# bpod_stepper_1_4_4.net
KiCad netlist of a schematic drawn in EAGLE
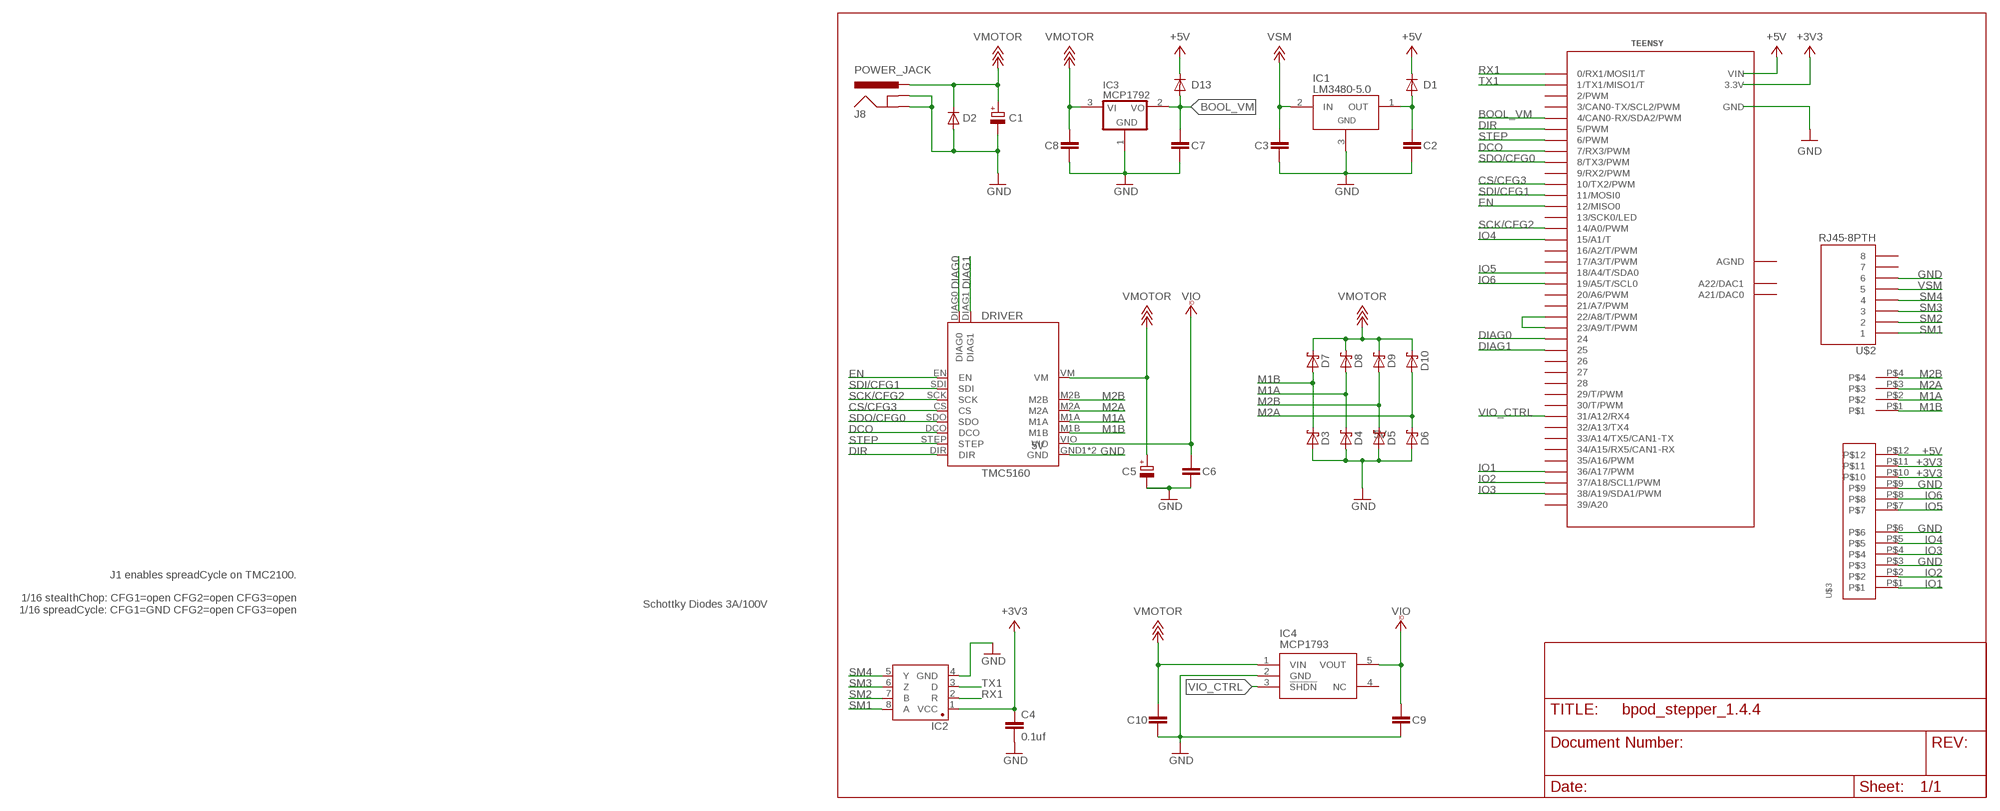
[diagram p0: schematic, sheet 1]

(export (version "E")
  (design (tool "Eeschema 10.0.6"))
  (components
    (comp (ref "C1")
      (value "CPOL-EUG")
      (footprint "eagle-import:PANASONIC_G")
      (libsource (lib "eagle-import") (part "CPOL-EUG"))
    )
    (comp (ref "C2")
      (value "0.1uf")
      (footprint "eagle-import:1206@1")
      (libsource (lib "eagle-import") (part "CAP1206"))
    )
    (comp (ref "C3")
      (value "0.1uf")
      (footprint "eagle-import:1206@1")
      (libsource (lib "eagle-import") (part "CAP1206"))
    )
    (comp (ref "C4")
      (value "0.1uf")
      (footprint "eagle-import:1206@1")
      (libsource (lib "eagle-import") (part "CAP1206"))
    )
    (comp (ref "C5")
      (value "CPOL-EUG")
      (footprint "eagle-import:PANASONIC_G")
      (libsource (lib "eagle-import") (part "CPOL-EUG"))
    )
    (comp (ref "C6")
      (value "0.1nf")
      (footprint "eagle-import:1206@1")
      (libsource (lib "eagle-import") (part "CAP1206"))
    )
    (comp (ref "C7")
      (value "2.2uf")
      (footprint "eagle-import:1206@1")
      (libsource (lib "eagle-import") (part "CAP1206"))
    )
    (comp (ref "C8")
      (value "2.2uf")
      (footprint "eagle-import:1206@1")
      (libsource (lib "eagle-import") (part "CAP1206"))
    )
    (comp (ref "C9")
      (value "2.2uf")
      (footprint "eagle-import:1206@1")
      (libsource (lib "eagle-import") (part "CAP1206"))
    )
    (comp (ref "C10")
      (value "2.2uf")
      (footprint "eagle-import:1206@1")
      (libsource (lib "eagle-import") (part "CAP1206"))
    )
    (comp (ref "D1")
      (value "MBR0520LT")
      (footprint "eagle-import:SOD123")
      (libsource (lib "eagle-import") (part "MBR0520LT"))
    )
    (comp (ref "D2")
      (value "DIODE-DO214AA")
      (footprint "eagle-import:DO214AA")
      (libsource (lib "eagle-import") (part "DIODE-DO214AA"))
    )
    (comp (ref "D3")
      (value "S310FA")
      (footprint "eagle-import:SOD123")
      (libsource (lib "eagle-import") (part "D_SCHOTTKY-SOD123"))
    )
    (comp (ref "D4")
      (value "S310FA")
      (footprint "eagle-import:SOD123")
      (libsource (lib "eagle-import") (part "D_SCHOTTKY-SOD123"))
    )
    (comp (ref "D5")
      (value "S310FA")
      (footprint "eagle-import:SOD123")
      (libsource (lib "eagle-import") (part "D_SCHOTTKY-SOD123"))
    )
    (comp (ref "D6")
      (value "S310FA")
      (footprint "eagle-import:SOD123")
      (libsource (lib "eagle-import") (part "D_SCHOTTKY-SOD123"))
    )
    (comp (ref "D7")
      (value "S310FA")
      (footprint "eagle-import:SOD123")
      (libsource (lib "eagle-import") (part "D_SCHOTTKY-SOD123"))
    )
    (comp (ref "D8")
      (value "S310FA")
      (footprint "eagle-import:SOD123")
      (libsource (lib "eagle-import") (part "D_SCHOTTKY-SOD123"))
    )
    (comp (ref "D9")
      (value "S310FA")
      (footprint "eagle-import:SOD123")
      (libsource (lib "eagle-import") (part "D_SCHOTTKY-SOD123"))
    )
    (comp (ref "D10")
      (value "S310FA")
      (footprint "eagle-import:SOD123")
      (libsource (lib "eagle-import") (part "D_SCHOTTKY-SOD123"))
    )
    (comp (ref "D13")
      (value "MBR0520LT")
      (footprint "eagle-import:SOD123")
      (libsource (lib "eagle-import") (part "MBR0520LT"))
    )
    (comp (ref "DRIVER")
      (value "TMC5160")
      (footprint "eagle-import:TMC5160")
      (libsource (lib "eagle-import") (part "TMC5160"))
    )
    (comp (ref "IC1")
      (value "LM3480-5.0")
      (footprint "eagle-import:SOT-23-3")
      (libsource (lib "eagle-import") (part "LM3480-5.0"))
    )
    (comp (ref "IC2")
      (value "SN65HVD31DR")
      (footprint "eagle-import:SO08")
      (libsource (lib "eagle-import") (part "SN65HVD31DR"))
    )
    (comp (ref "IC3")
      (value "MCP1792")
      (footprint "eagle-import:SOT23A_MICROCHIP_CB")
      (libsource (lib "eagle-import") (part "MCP170302E/CB-12"))
    )
    (comp (ref "IC4")
      (value "MCP1793")
      (footprint "eagle-import:SOT23-5")
      (libsource (lib "eagle-import") (part "MCP1793"))
    )
    (comp (ref "J8")
      (value "POWER_JACK")
      (footprint "eagle-import:POWER_JACK_PTH")
      (libsource (lib "eagle-import") (part "POWER_JACK"))
    )
    (comp (ref "TEENSY")
      (value "TEENSY_3.6_DIL")
      (footprint "eagle-import:TEENSY_3.6_DIL")
      (libsource (lib "eagle-import") (part "TEENSY_3.6_DIL"))
    )
    (comp (ref "U$2")
      (value "RJ45-8PTH")
      (footprint "eagle-import:RJ45-8")
      (libsource (lib "eagle-import") (part "RJ45-8PTH"))
    )
    (comp (ref "U$3")
      (value "12POS_MOLEX_SOCKET")
      (footprint "eagle-import:12POS_MOLEX_SOCKET")
      (libsource (lib "eagle-import") (part "12POS_MOLEX_SOCKET"))
    )
    (comp (ref "U$4")
      (value "MOLEX395221004")
      (footprint "eagle-import:MOLEX395221004")
      (libsource (lib "eagle-import") (part "MOLEX395221004"))
    )
  )
  (nets
    (net (code "1") (name "+3V3") (class "Default")
      (node (ref "C4") (pin "1") (pinfunction "1_1") (pintype "passive"))
      (node (ref "IC2") (pin "1") (pinfunction "VCC_1") (pintype "bidirectional"))
      (node (ref "TEENSY") (pin "3.3V") (pinfunction "3.3V_3.3V") (pintype "power_in"))
      (node (ref "TEENSY") (pin "3.3V3") (pinfunction "3.3V_3.3V3") (pintype "power_in"))
      (node (ref "U$3") (pin "P$10") (pinfunction "P$10_P$10") (pintype "bidirectional"))
      (node (ref "U$3") (pin "P$11") (pinfunction "P$11_P$11") (pintype "bidirectional"))
    )
    (net (code "2") (name "+5V") (class "Default")
      (node (ref "D1") (pin "C") (pinfunction "C_C") (pintype "passive"))
      (node (ref "D13") (pin "C") (pinfunction "C_C") (pintype "passive"))
      (node (ref "TEENSY") (pin "VIN") (pinfunction "VIN_VIN") (pintype "power_in"))
      (node (ref "U$3") (pin "P$12") (pinfunction "P$12_P$12") (pintype "bidirectional"))
    )
    (net (code "3") (name "+12V") (class "Default")
      (node (ref "C3") (pin "2") (pinfunction "2_2") (pintype "passive"))
      (node (ref "IC1") (pin "2") (pinfunction "IN_2") (pintype "power_in"))
      (node (ref "U$2") (pin "5") (pinfunction "5_5") (pintype "bidirectional"))
    )
    (net (code "4") (name "+18V") (class "Default")
      (node (ref "C1") (pin "+") (pinfunction "+_+") (pintype "passive"))
      (node (ref "C10") (pin "2") (pinfunction "2_2") (pintype "passive"))
      (node (ref "C5") (pin "+") (pinfunction "+_+") (pintype "passive"))
      (node (ref "C8") (pin "2") (pinfunction "2_2") (pintype "passive"))
      (node (ref "D10") (pin "C") (pinfunction "C_C") (pintype "passive"))
      (node (ref "D2") (pin "C") (pinfunction "C_C") (pintype "passive"))
      (node (ref "D7") (pin "C") (pinfunction "C_C") (pintype "passive"))
      (node (ref "D8") (pin "C") (pinfunction "C_C") (pintype "passive"))
      (node (ref "D9") (pin "C") (pinfunction "C_C") (pintype "passive"))
      (node (ref "DRIVER") (pin "VM") (pinfunction "VM_VM") (pintype "power_in"))
      (node (ref "IC3") (pin "3") (pinfunction "VI_3") (pintype "power_in"))
      (node (ref "IC4") (pin "1") (pinfunction "VIN_1") (pintype "bidirectional"))
      (node (ref "J8") (pin "PWR") (pinfunction "PWR_PWR") (pintype "bidirectional"))
    )
    (net (code "5") (name "/AGND") (class "Default")
      (node (ref "TEENSY") (pin "AGND") (pinfunction "AGND_AGND") (pintype "power_in"))
    )
    (net (code "6") (name "/CS{slash}CFG3") (class "Default")
      (node (ref "DRIVER") (pin "CS") (pinfunction "CS_CS") (pintype "passive"))
      (node (ref "TEENSY") (pin "10") (pinfunction "10/TX2/PWM_10") (pintype "bidirectional"))
    )
    (net (code "7") (name "/DCO") (class "Default")
      (node (ref "DRIVER") (pin "DCO") (pinfunction "DCO_DCO") (pintype "passive"))
      (node (ref "TEENSY") (pin "7") (pinfunction "7/RX3/PWM_7") (pintype "bidirectional"))
    )
    (net (code "8") (name "/DIAG0") (class "Default")
      (node (ref "DRIVER") (pin "DIAG0") (pinfunction "DIAG0_DIAG0") (pintype "passive"))
      (node (ref "TEENSY") (pin "24") (pinfunction "24_24") (pintype "bidirectional"))
    )
    (net (code "9") (name "/DIAG1") (class "Default")
      (node (ref "DRIVER") (pin "DIAG1") (pinfunction "DIAG1_DIAG1") (pintype "passive"))
      (node (ref "TEENSY") (pin "25") (pinfunction "25_25") (pintype "bidirectional"))
    )
    (net (code "10") (name "/DIR") (class "Default")
      (node (ref "DRIVER") (pin "DIR") (pinfunction "DIR_DIR") (pintype "input"))
      (node (ref "TEENSY") (pin "5") (pinfunction "5/PWM_5") (pintype "bidirectional"))
    )
    (net (code "11") (name "/EN") (class "Default")
      (node (ref "DRIVER") (pin "EN") (pinfunction "EN_EN") (pintype "passive"))
      (node (ref "TEENSY") (pin "12") (pinfunction "12/MISO0_12") (pintype "bidirectional"))
    )
    (net (code "12") (name "/IO1") (class "Default")
      (node (ref "TEENSY") (pin "36/A17") (pinfunction "36/A17/PWM_36/A17") (pintype "bidirectional"))
      (node (ref "U$3") (pin "P$1") (pinfunction "P$1_P$1") (pintype "bidirectional"))
    )
    (net (code "13") (name "/IO2") (class "Default")
      (node (ref "TEENSY") (pin "37/A18") (pinfunction "37/A18/SCL1/PWM_37/A18") (pintype "bidirectional"))
      (node (ref "U$3") (pin "P$2") (pinfunction "P$2_P$2") (pintype "bidirectional"))
    )
    (net (code "14") (name "/IO3") (class "Default")
      (node (ref "TEENSY") (pin "38/A19") (pinfunction "38/A19/SDA1/PWM_38/A19") (pintype "bidirectional"))
      (node (ref "U$3") (pin "P$4") (pinfunction "P$4_P$4") (pintype "bidirectional"))
    )
    (net (code "15") (name "/IO4") (class "Default")
      (node (ref "TEENSY") (pin "15/A1") (pinfunction "15/A1/T_15/A1") (pintype "bidirectional"))
      (node (ref "U$3") (pin "P$5") (pinfunction "P$5_P$5") (pintype "bidirectional"))
    )
    (net (code "16") (name "/IO5") (class "Default")
      (node (ref "TEENSY") (pin "18/A4") (pinfunction "18/A4/T/SDA0_18/A4") (pintype "bidirectional"))
      (node (ref "U$3") (pin "P$7") (pinfunction "P$7_P$7") (pintype "bidirectional"))
    )
    (net (code "17") (name "/IO6") (class "Default")
      (node (ref "TEENSY") (pin "19/A5") (pinfunction "19/A5/T/SCL0_19/A5") (pintype "bidirectional"))
      (node (ref "U$3") (pin "P$8") (pinfunction "P$8_P$8") (pintype "bidirectional"))
    )
    (net (code "18") (name "/M1A") (class "Default")
      (node (ref "D4") (pin "C") (pinfunction "C_C") (pintype "passive"))
      (node (ref "D8") (pin "A") (pinfunction "A_A") (pintype "passive"))
      (node (ref "DRIVER") (pin "M1A") (pinfunction "M1A_M1A") (pintype "output"))
      (node (ref "U$4") (pin "P$2") (pinfunction "P$2_P$2") (pintype "bidirectional"))
    )
    (net (code "19") (name "/M1B") (class "Default")
      (node (ref "D3") (pin "C") (pinfunction "C_C") (pintype "passive"))
      (node (ref "D7") (pin "A") (pinfunction "A_A") (pintype "passive"))
      (node (ref "DRIVER") (pin "M1B") (pinfunction "M1B_M1B") (pintype "output"))
      (node (ref "U$4") (pin "P$1") (pinfunction "P$1_P$1") (pintype "bidirectional"))
    )
    (net (code "20") (name "/M2A") (class "Default")
      (node (ref "D10") (pin "A") (pinfunction "A_A") (pintype "passive"))
      (node (ref "D6") (pin "C") (pinfunction "C_C") (pintype "passive"))
      (node (ref "DRIVER") (pin "M2A") (pinfunction "M2A_M2A") (pintype "output"))
      (node (ref "U$4") (pin "P$3") (pinfunction "P$3_P$3") (pintype "bidirectional"))
    )
    (net (code "21") (name "/M2B") (class "Default")
      (node (ref "D5") (pin "C") (pinfunction "C_C") (pintype "passive"))
      (node (ref "D9") (pin "A") (pinfunction "A_A") (pintype "passive"))
      (node (ref "DRIVER") (pin "M2B") (pinfunction "M2B_M2B") (pintype "output"))
      (node (ref "U$4") (pin "P$4") (pinfunction "P$4_P$4") (pintype "bidirectional"))
    )
    (net (code "22") (name "/RX1") (class "Default")
      (node (ref "IC2") (pin "2") (pinfunction "R_2") (pintype "bidirectional"))
      (node (ref "TEENSY") (pin "0") (pinfunction "0/RX1/MOSI1/T_0") (pintype "bidirectional"))
    )
    (net (code "23") (name "/SCK{slash}CFG2") (class "Default")
      (node (ref "DRIVER") (pin "SCK") (pinfunction "SCK_SCK") (pintype "passive"))
      (node (ref "TEENSY") (pin "14/A0") (pinfunction "14/A0/PWM_14/A0") (pintype "bidirectional"))
    )
    (net (code "24") (name "/SDI{slash}CFG1") (class "Default")
      (node (ref "DRIVER") (pin "SDI") (pinfunction "SDI_SDI") (pintype "passive"))
      (node (ref "TEENSY") (pin "11") (pinfunction "11/MOSI0_11") (pintype "bidirectional"))
    )
    (net (code "25") (name "/SDO{slash}CFG0") (class "Default")
      (node (ref "DRIVER") (pin "SDO") (pinfunction "SDO_SDO") (pintype "passive"))
      (node (ref "TEENSY") (pin "8") (pinfunction "8/TX3/PWM_8") (pintype "bidirectional"))
    )
    (net (code "26") (name "/SM1") (class "Default")
      (node (ref "IC2") (pin "8") (pinfunction "A_8") (pintype "bidirectional"))
      (node (ref "U$2") (pin "1") (pinfunction "1_1") (pintype "bidirectional"))
    )
    (net (code "27") (name "/SM2") (class "Default")
      (node (ref "IC2") (pin "7") (pinfunction "B_7") (pintype "bidirectional"))
      (node (ref "U$2") (pin "2") (pinfunction "2_2") (pintype "bidirectional"))
    )
    (net (code "28") (name "/SM3") (class "Default")
      (node (ref "IC2") (pin "6") (pinfunction "Z_6") (pintype "bidirectional"))
      (node (ref "U$2") (pin "3") (pinfunction "3_3") (pintype "bidirectional"))
    )
    (net (code "29") (name "/SM4") (class "Default")
      (node (ref "IC2") (pin "5") (pinfunction "Y_5") (pintype "bidirectional"))
      (node (ref "U$2") (pin "4") (pinfunction "4_4") (pintype "bidirectional"))
    )
    (net (code "30") (name "/STEP") (class "Default")
      (node (ref "DRIVER") (pin "STEP") (pinfunction "STEP_STEP") (pintype "input"))
      (node (ref "TEENSY") (pin "6") (pinfunction "6/PWM_6") (pintype "bidirectional"))
    )
    (net (code "31") (name "/TX1") (class "Default")
      (node (ref "IC2") (pin "3") (pinfunction "D_3") (pintype "bidirectional"))
      (node (ref "TEENSY") (pin "1") (pinfunction "1/TX1/MISO1/T_1") (pintype "bidirectional"))
    )
    (net (code "32") (name "BOOL_VM") (class "Default")
      (node (ref "C7") (pin "2") (pinfunction "2_2") (pintype "passive"))
      (node (ref "D13") (pin "A") (pinfunction "A_A") (pintype "passive"))
      (node (ref "IC3") (pin "2") (pinfunction "VO_2") (pintype "passive"))
      (node (ref "TEENSY") (pin "4") (pinfunction "4/CAN0-RX/SDA2/PWM_4") (pintype "bidirectional"))
    )
    (net (code "33") (name "GND") (class "Default")
      (node (ref "C1") (pin "-") (pinfunction "-_-") (pintype "passive"))
      (node (ref "C10") (pin "1") (pinfunction "1_1") (pintype "passive"))
      (node (ref "C2") (pin "1") (pinfunction "1_1") (pintype "passive"))
      (node (ref "C3") (pin "1") (pinfunction "1_1") (pintype "passive"))
      (node (ref "C4") (pin "2") (pinfunction "2_2") (pintype "passive"))
      (node (ref "C5") (pin "-") (pinfunction "-_-") (pintype "passive"))
      (node (ref "C6") (pin "2") (pinfunction "2_2") (pintype "passive"))
      (node (ref "C7") (pin "1") (pinfunction "1_1") (pintype "passive"))
      (node (ref "C8") (pin "1") (pinfunction "1_1") (pintype "passive"))
      (node (ref "C9") (pin "1") (pinfunction "1_1") (pintype "passive"))
      (node (ref "D2") (pin "A") (pinfunction "A_A") (pintype "passive"))
      (node (ref "D3") (pin "A") (pinfunction "A_A") (pintype "passive"))
      (node (ref "D4") (pin "A") (pinfunction "A_A") (pintype "passive"))
      (node (ref "D5") (pin "A") (pinfunction "A_A") (pintype "passive"))
      (node (ref "D6") (pin "A") (pinfunction "A_A") (pintype "passive"))
      (node (ref "DRIVER") (pin "GND1") (pinfunction "GND_GND1") (pintype "power_in"))
      (node (ref "DRIVER") (pin "GND2") (pinfunction "GND_GND2") (pintype "power_in"))
      (node (ref "IC1") (pin "3") (pinfunction "GND_3") (pintype "power_in"))
      (node (ref "IC2") (pin "4") (pinfunction "GND_4") (pintype "bidirectional"))
      (node (ref "IC3") (pin "1") (pinfunction "GND_1") (pintype "power_in"))
      (node (ref "IC4") (pin "2") (pinfunction "GND_2") (pintype "bidirectional"))
      (node (ref "J8") (pin "GND") (pinfunction "GND_GND") (pintype "bidirectional"))
      (node (ref "J8") (pin "GNDBREAK") (pinfunction "GNDBREAK_GNDBREAK") (pintype "bidirectional"))
      (node (ref "TEENSY") (pin "GND") (pinfunction "GND_GND") (pintype "power_in"))
      (node (ref "TEENSY") (pin "GND1") (pinfunction "GND_GND1") (pintype "power_in"))
      (node (ref "U$2") (pin "6") (pinfunction "6_6") (pintype "bidirectional"))
      (node (ref "U$3") (pin "P$3") (pinfunction "P$3_P$3") (pintype "bidirectional"))
      (node (ref "U$3") (pin "P$6") (pinfunction "P$6_P$6") (pintype "bidirectional"))
      (node (ref "U$3") (pin "P$9") (pinfunction "P$9_P$9") (pintype "bidirectional"))
    )
    (net (code "34") (name "Net-(IC1-OUT)") (class "Default")
      (node (ref "C2") (pin "2") (pinfunction "2_2") (pintype "passive"))
      (node (ref "D1") (pin "A") (pinfunction "A_A") (pintype "passive"))
      (node (ref "IC1") (pin "1") (pinfunction "OUT_1") (pintype "power_in"))
    )
    (net (code "35") (name "Net-(TEENSY-22{slash}A8{slash}T{slash}PWM)") (class "Default")
      (node (ref "TEENSY") (pin "22/A8") (pinfunction "22/A8/T/PWM_22/A8") (pintype "bidirectional"))
      (node (ref "TEENSY") (pin "23/A9") (pinfunction "23/A9/T/PWM_23/A9") (pintype "bidirectional"))
    )
    (net (code "36") (name "VCCIO") (class "Default")
      (node (ref "C6") (pin "1") (pinfunction "1_1") (pintype "passive"))
      (node (ref "C9") (pin "2") (pinfunction "2_2") (pintype "passive"))
      (node (ref "DRIVER") (pin "VIO") (pinfunction "VIO_VIO") (pintype "power_in"))
      (node (ref "IC4") (pin "5") (pinfunction "VOUT_5") (pintype "bidirectional"))
    )
    (net (code "37") (name "VIO_CTRL") (class "Default")
      (node (ref "IC4") (pin "3") (pinfunction "~{SHDN}_3") (pintype "bidirectional"))
      (node (ref "TEENSY") (pin "31/A12") (pinfunction "31/A12/RX4_31/A12") (pintype "bidirectional"))
    )
    (net (code "38") (name "unconnected-(IC4-NC-Pad4)") (class "Default")
      (node (ref "IC4") (pin "4") (pinfunction "NC_4") (pintype "bidirectional"))
    )
    (net (code "39") (name "unconnected-(TEENSY-2{slash}PWM-Pad2)") (class "Default")
      (node (ref "TEENSY") (pin "2") (pinfunction "2/PWM_2") (pintype "bidirectional"))
    )
    (net (code "40") (name "unconnected-(TEENSY-3{slash}CAN0-TX{slash}SCL2{slash}PWM-Pad3)") (class "Default")
      (node (ref "TEENSY") (pin "3") (pinfunction "3/CAN0-TX/SCL2/PWM_3") (pintype "bidirectional"))
    )
    (net (code "41") (name "unconnected-(TEENSY-9{slash}RX2{slash}PWM-Pad9)") (class "Default")
      (node (ref "TEENSY") (pin "9") (pinfunction "9/RX2/PWM_9") (pintype "bidirectional"))
    )
    (net (code "42") (name "unconnected-(TEENSY-13{slash}SCK0{slash}LED-Pad13)") (class "Default")
      (node (ref "TEENSY") (pin "13") (pinfunction "13/SCK0/LED_13") (pintype "bidirectional"))
    )
    (net (code "43") (name "unconnected-(TEENSY-16{slash}A2{slash}T{slash}PWM-Pad16{slash}A2)") (class "Default")
      (node (ref "TEENSY") (pin "16/A2") (pinfunction "16/A2/T/PWM_16/A2") (pintype "bidirectional"))
    )
    (net (code "44") (name "unconnected-(TEENSY-17{slash}A3{slash}T{slash}PWM-Pad17{slash}A3)") (class "Default")
      (node (ref "TEENSY") (pin "17/A3") (pinfunction "17/A3/T/PWM_17/A3") (pintype "bidirectional"))
    )
    (net (code "45") (name "unconnected-(TEENSY-20{slash}A6{slash}PWM-Pad20{slash}A6)") (class "Default")
      (node (ref "TEENSY") (pin "20/A6") (pinfunction "20/A6/PWM_20/A6") (pintype "bidirectional"))
    )
    (net (code "46") (name "unconnected-(TEENSY-21{slash}A7{slash}PWM-Pad21{slash}A7)") (class "Default")
      (node (ref "TEENSY") (pin "21/A7") (pinfunction "21/A7/PWM_21/A7") (pintype "bidirectional"))
    )
    (net (code "47") (name "unconnected-(TEENSY-29{slash}T{slash}PWM-Pad29)") (class "Default")
      (node (ref "TEENSY") (pin "29") (pinfunction "29/T/PWM_29") (pintype "bidirectional"))
    )
    (net (code "48") (name "unconnected-(TEENSY-30{slash}T{slash}PWM-Pad30)") (class "Default")
      (node (ref "TEENSY") (pin "30") (pinfunction "30/T/PWM_30") (pintype "bidirectional"))
    )
    (net (code "49") (name "unconnected-(TEENSY-32{slash}A13{slash}TX4-Pad32{slash}A13)") (class "Default")
      (node (ref "TEENSY") (pin "32/A13") (pinfunction "32/A13/TX4_32/A13") (pintype "bidirectional"))
    )
    (net (code "50") (name "unconnected-(TEENSY-33{slash}A14{slash}TX5{slash}CAN1-TX-Pad33{slash}A14)") (class "Default")
      (node (ref "TEENSY") (pin "33/A14") (pinfunction "33/A14/TX5/CAN1-TX_33/A14") (pintype "bidirectional"))
    )
    (net (code "51") (name "unconnected-(TEENSY-34{slash}A15{slash}RX5{slash}CAN1-RX-Pad34{slash}A15)") (class "Default")
      (node (ref "TEENSY") (pin "34/A15") (pinfunction "34/A15/RX5/CAN1-RX_34/A15") (pintype "bidirectional"))
    )
    (net (code "52") (name "unconnected-(TEENSY-35{slash}A16{slash}PWM-Pad35{slash}A16)") (class "Default")
      (node (ref "TEENSY") (pin "35/A16") (pinfunction "35/A16/PWM_35/A16") (pintype "bidirectional"))
    )
    (net (code "53") (name "unconnected-(TEENSY-A21{slash}DAC0-PadA21)") (class "Default")
      (node (ref "TEENSY") (pin "A21") (pinfunction "A21/DAC0_A21") (pintype "bidirectional"))
    )
    (net (code "54") (name "unconnected-(TEENSY-A22{slash}DAC1-PadA22)") (class "Default")
      (node (ref "TEENSY") (pin "A22") (pinfunction "A22/DAC1_A22") (pintype "bidirectional"))
    )
    (net (code "55") (name "unconnected-(TEENSY-Pad26)") (class "Default")
      (node (ref "TEENSY") (pin "26") (pinfunction "26_26") (pintype "bidirectional"))
    )
    (net (code "56") (name "unconnected-(TEENSY-Pad27)") (class "Default")
      (node (ref "TEENSY") (pin "27") (pinfunction "27_27") (pintype "bidirectional"))
    )
    (net (code "57") (name "unconnected-(TEENSY-Pad28)") (class "Default")
      (node (ref "TEENSY") (pin "28") (pinfunction "28_28") (pintype "bidirectional"))
    )
    (net (code "58") (name "unconnected-(TEENSY-Pad39{slash}A20)") (class "Default")
      (node (ref "TEENSY") (pin "39/A20") (pinfunction "39/A20_39/A20") (pintype "bidirectional"))
    )
    (net (code "59") (name "unconnected-(U$2-Pad7)") (class "Default")
      (node (ref "U$2") (pin "7") (pinfunction "7_7") (pintype "bidirectional"))
    )
    (net (code "60") (name "unconnected-(U$2-Pad8)") (class "Default")
      (node (ref "U$2") (pin "8") (pinfunction "8_8") (pintype "bidirectional"))
    )
  )
)
